# Power_Management.net
KiCad netlist of a schematic drawn in Altium Designer
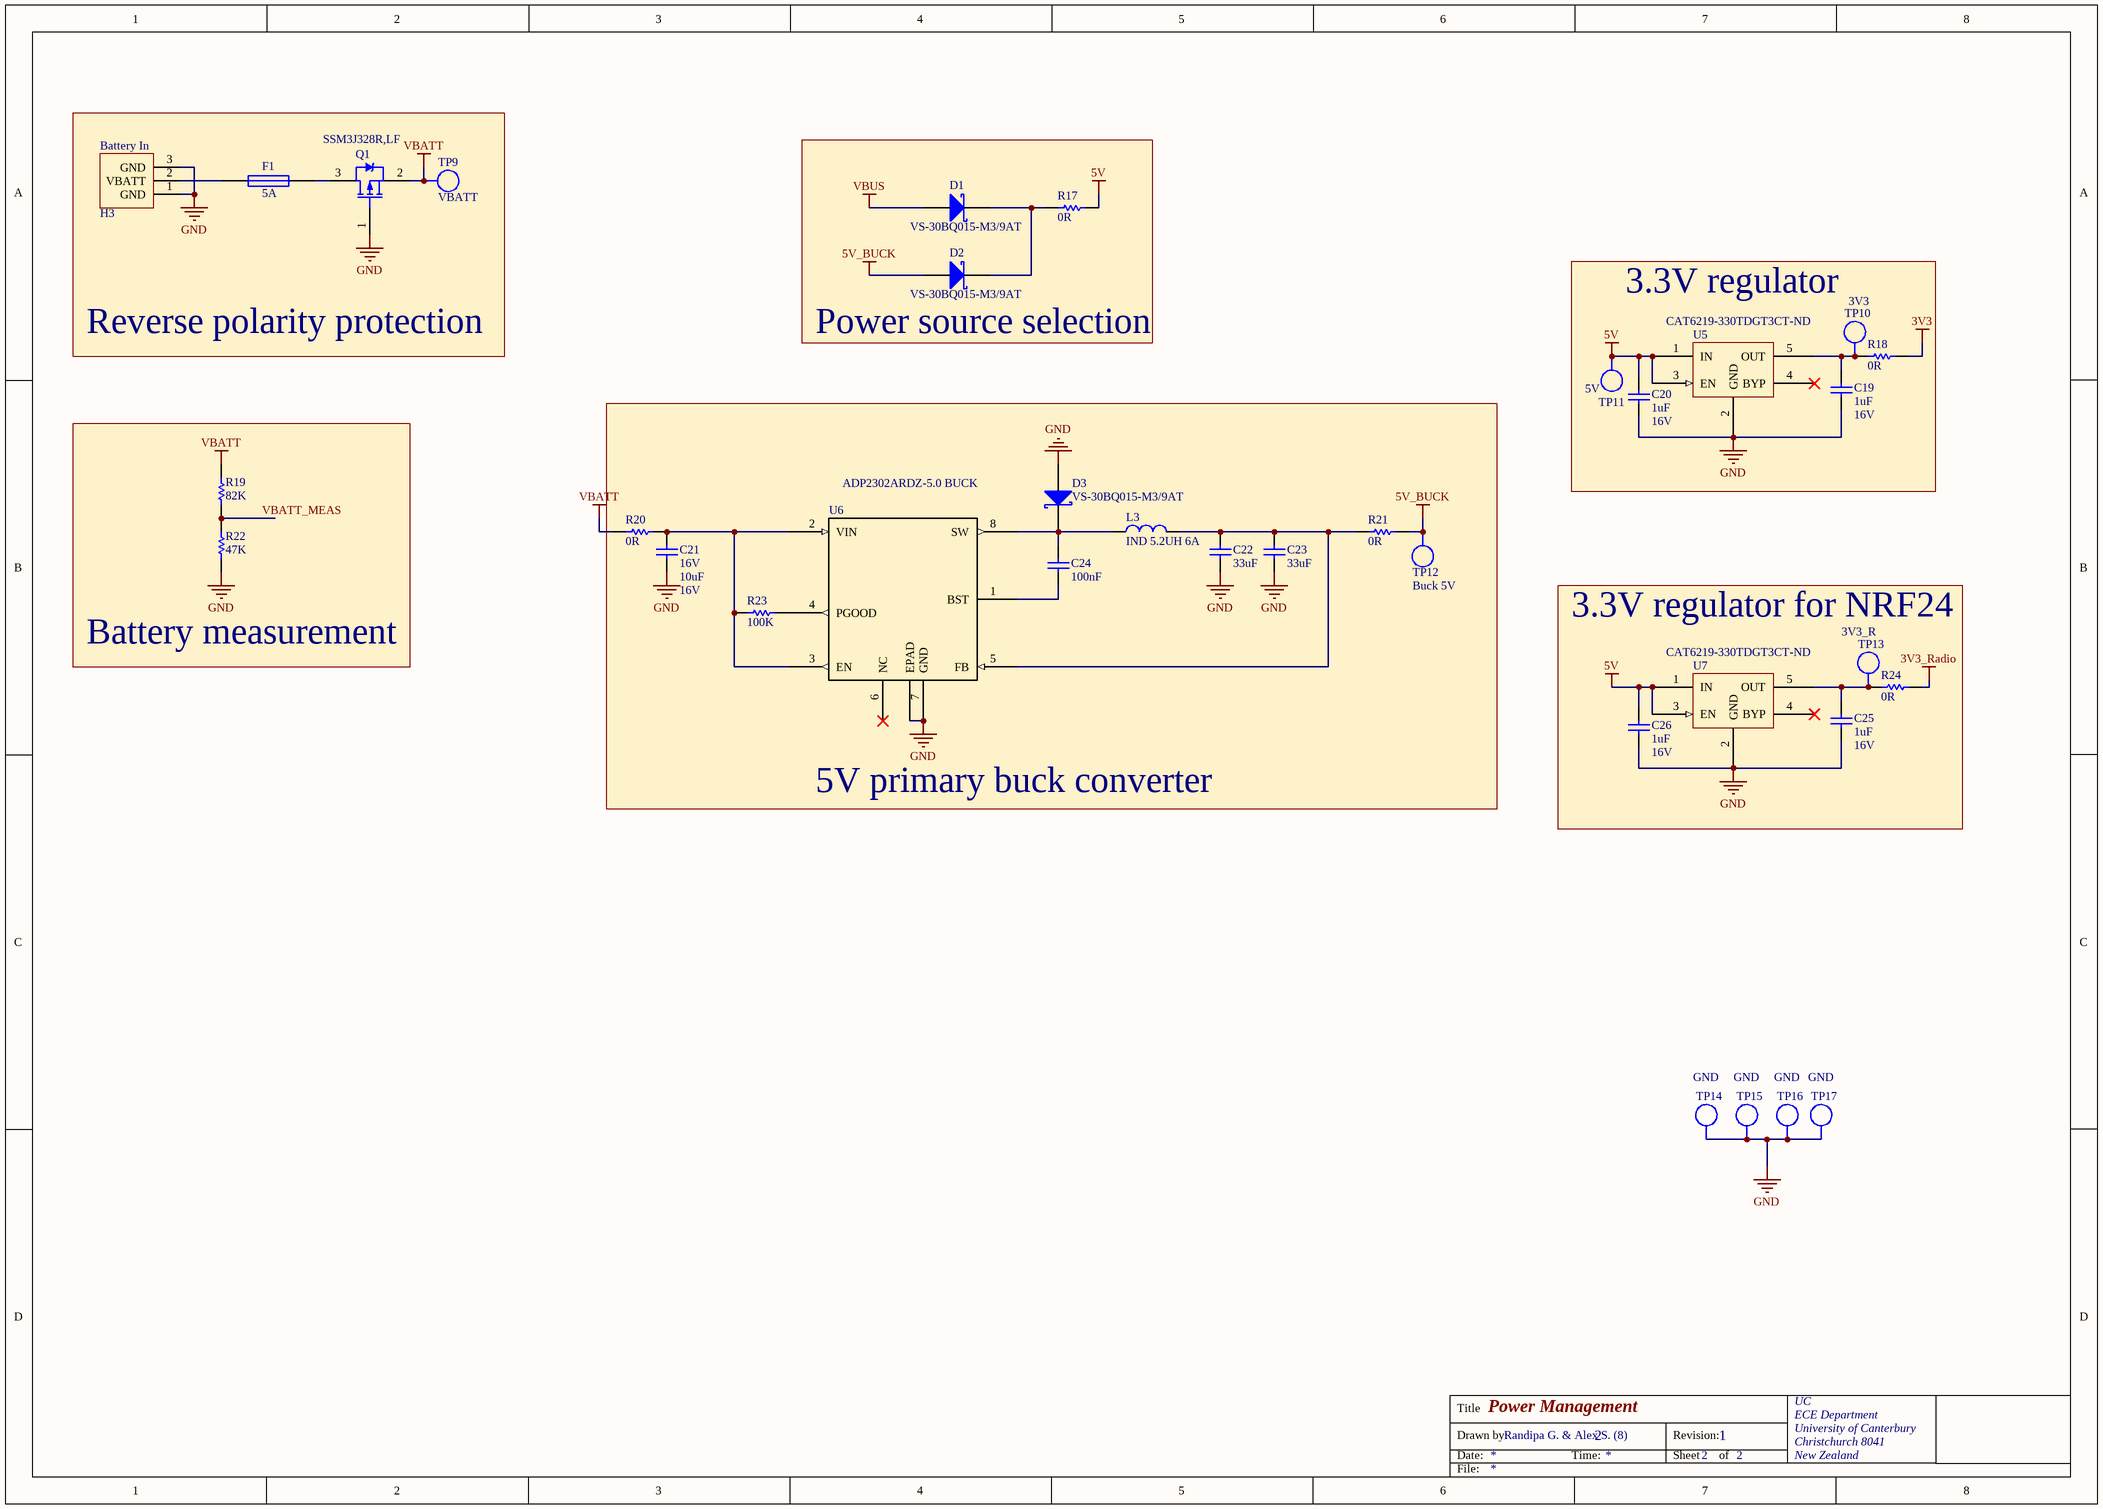
[diagram p0: Power Management.SchDoc]

(export (version "E")
  (design (tool "Eeschema 10.0.6"))
  (components
    (comp (ref "C19")
      (value "1uF")
      (footprint "CAPC1608L")
      (description "CAP CER 1uF Y5V -20% +80% 16V 0603")
      (fields (field (name "MAX VOLTAGE") "16V"))
      (libsource (lib "ECE AD19Components_19V1") (part "CC_1uF_0603"))
    )
    (comp (ref "C20")
      (value "1uF")
      (footprint "CAPC1608L")
      (description "CAP CER 1uF Y5V -20% +80% 16V 0603")
      (fields (field (name "MAX VOLTAGE") "16V"))
      (libsource (lib "ECE AD19Components_19V1") (part "CC_1uF_0603"))
    )
    (comp (ref "C21")
      (value "10uF")
      (footprint "CAPC2012L")
      (description "CAP CER 10uF X5R 16V 0805")
      (fields
        (field (name "MANUFACTURER") "Samsung Electro-Mechanics")
        (field (name "MANUFACTURER PART NUMBER") "CL21A106KOQNNWE")
        (field (name "VOLTAGE - RATED") "16V")
        (field (name "MAX VOLTAGE") "16V")
      )
      (libsource (lib "ENCE461AD19_19V2") (part "CC_10uF_16V_0805"))
    )
    (comp (ref "C22")
      (value "33uF")
      (footprint "CAPC2012L")
      (description "CAP CER 33uF X5R 6V3 0805")
      (fields
        (field (name "MANUFACTURER") "TDK Corporation")
        (field (name "MANUFACTURER PART NUMBER") "C2012X5R0J336M125AC")
      )
      (libsource (lib "ENCE461AD19_19V2") (part "CC_33uF_6V3_0805"))
    )
    (comp (ref "C23")
      (value "33uF")
      (footprint "CAPC2012L")
      (description "CAP CER 33uF X5R 6V3 0805")
      (fields
        (field (name "MANUFACTURER") "TDK Corporation")
        (field (name "MANUFACTURER PART NUMBER") "C2012X5R0J336M125AC")
      )
      (libsource (lib "ENCE461AD19_19V2") (part "CC_33uF_6V3_0805"))
    )
    (comp (ref "C24")
      (value "100nF")
      (footprint "CAPC1608L")
      (description "CAP CER 100nF X7R +-10% 50V 0603")
      (libsource (lib "ECE AD19Components_19V1") (part "CC_100nF_0603"))
    )
    (comp (ref "C25")
      (value "1uF")
      (footprint "CAPC1608L")
      (description "CAP CER 1uF Y5V -20% +80% 16V 0603")
      (fields (field (name "MAX VOLTAGE") "16V"))
      (libsource (lib "ECE AD19Components_19V1") (part "CC_1uF_0603"))
    )
    (comp (ref "C26")
      (value "1uF")
      (footprint "CAPC1608L")
      (description "CAP CER 1uF Y5V -20% +80% 16V 0603")
      (fields (field (name "MAX VOLTAGE") "16V"))
      (libsource (lib "ECE AD19Components_19V1") (part "CC_1uF_0603"))
    )
    (comp (ref "D1")
      (value "VS-30BQ015-M3/9AT")
      (footprint "SMC")
      (description "DIODE, SCHOTTKY, 3A, 15V, DO-214AB / SMC")
      (fields (field (name "MANUFACTURER") "Vishay Semiconductors"))
      (libsource (lib "ECE AD19Components_19V1") (part "DS_VS-30BQ015-M3"))
    )
    (comp (ref "D2")
      (value "VS-30BQ015-M3/9AT")
      (footprint "SMC")
      (description "DIODE, SCHOTTKY, 3A, 15V, DO-214AB / SMC")
      (fields (field (name "MANUFACTURER") "Vishay Semiconductors"))
      (libsource (lib "ECE AD19Components_19V1") (part "DS_VS-30BQ015-M3"))
    )
    (comp (ref "D3")
      (value "VS-30BQ015-M3/9AT")
      (footprint "SMC")
      (description "DIODE, SCHOTTKY, 3A, 15V, DO-214AB / SMC")
      (fields (field (name "MANUFACTURER") "Vishay Semiconductors"))
      (libsource (lib "ECE AD19Components_19V1") (part "DS_VS-30BQ015-M3"))
    )
    (comp (ref "F1")
      (value "5A")
      (footprint "RESC3216N")
      (description "Fuse 5.0A Fast Acting 1206 SMD")
      (fields (field (name "MANUFACTURER PART NUMBER") "C1F5") (field (name "MANUFACTURER") "Bel TRP"))
      (libsource (lib "ECE AD19Components_19V1") (part "FS_Fuse_5.0A"))
    )
    (comp (ref "H3")
      (value "Battery In")
      (footprint "BATT_HEADER_3POS")
      (description "3Pin Header 2.54mm spacing")
      (libsource (lib "ENCE461AD19_19V2") (part "Battery_HEADER_3pin"))
    )
    (comp (ref "L3")
      (value "IND 5.2UH 6A")
      (footprint "INDUCTOR5u2")
      (description "FIXED IND 5.2UH 6A 22 MOHM SMD")
      (fields
        (field (name "MANUFACTURER") "Sumida America Components Inc.")
        (field (name "MANUFACTURER PART NUMBER") "CDRH104RNP-5R2NC")
      )
      (libsource (lib "ENCE461AD19_19V2") (part "CDRH104RNP-5R2NC"))
    )
    (comp (ref "Q1")
      (value "SSM3J328R,LF")
      (footprint "SOT23_L")
      (description "MOSFET P-CH 20V 6A SOT23-3")
      (fields
        (field (name "MANUFACTURER") "Toshiba")
        (field (name "MANUFACTURER PART NUMBER") "SSM3J328R,LF")
      )
      (libsource (lib "ECE AD19Components_19V1") (part "TM_SSM3J328R"))
    )
    (comp (ref "R17")
      (value "0R")
      (footprint "RESC1608L")
      (description "RES 0.0 OHM 1/10W 5% 0603 SMD")
      (libsource (lib "ECE AD19Components_19V1") (part "RS_0R0"))
    )
    (comp (ref "R18")
      (value "0R")
      (footprint "RESC1608L")
      (description "RES 0.0 OHM 1/10W 5% 0603 SMD")
      (libsource (lib "ECE AD19Components_19V1") (part "RS_0R0"))
    )
    (comp (ref "R19")
      (value "82K")
      (footprint "RESC1608L")
      (description "RES 82.0K OHM 1/10W 5% 0603 SMD")
      (libsource (lib "ECE AD19Components_19V1") (part "RS_82K"))
    )
    (comp (ref "R20")
      (value "0R")
      (footprint "RESC1608L")
      (description "RES 0.0 OHM 1/10W 5% 0603 SMD")
      (libsource (lib "ECE AD19Components_19V1") (part "RS_0R0"))
    )
    (comp (ref "R21")
      (value "0R")
      (footprint "RESC1608L")
      (description "RES 0.0 OHM 1/10W 5% 0603 SMD")
      (libsource (lib "ECE AD19Components_19V1") (part "RS_0R0"))
    )
    (comp (ref "R22")
      (value "47K")
      (footprint "RESC1608L")
      (description "RES 47.0K OHM 1/10W 5% 0603 SMD")
      (libsource (lib "ECE AD19Components_19V1") (part "RS_47K"))
    )
    (comp (ref "R23")
      (value "100K")
      (footprint "RESC1608L")
      (description "RES 100K OHM 1/10W 5% 0603 SMD")
      (libsource (lib "ECE AD19Components_19V1") (part "RS_100K"))
    )
    (comp (ref "R24")
      (value "0R")
      (footprint "RESC1608L")
      (description "RES 0.0 OHM 1/10W 5% 0603 SMD")
      (libsource (lib "ECE AD19Components_19V1") (part "RS_0R0"))
    )
    (comp (ref "TP9")
      (value "VBATT")
      (footprint "TP_1206")
      (description "Test-Point 3.3x1.6x2.1mm SMD")
      (fields
        (field (name "MANUFACTURER") "Harwin Inc")
        (field (name "MANUFACTURER PART NUMBER") "S1751-46R")
      )
      (libsource (lib "ECE AD19Components_19V1") (part "TP_1206"))
    )
    (comp (ref "TP10")
      (value "3V3")
      (footprint "TP_1206")
      (description "Test-Point 3.3x1.6x2.1mm SMD")
      (fields
        (field (name "MANUFACTURER") "Harwin Inc")
        (field (name "MANUFACTURER PART NUMBER") "S1751-46R")
      )
      (libsource (lib "ECE AD19Components_19V1") (part "TP_1206"))
    )
    (comp (ref "TP11")
      (value "5V")
      (footprint "TP_1206")
      (description "Test-Point 3.3x1.6x2.1mm SMD")
      (fields
        (field (name "MANUFACTURER") "Harwin Inc")
        (field (name "MANUFACTURER PART NUMBER") "S1751-46R")
      )
      (libsource (lib "ECE AD19Components_19V1") (part "TP_1206"))
    )
    (comp (ref "TP12")
      (value "Buck 5V")
      (footprint "TP_1206")
      (description "Test-Point 3.3x1.6x2.1mm SMD")
      (fields
        (field (name "MANUFACTURER") "Harwin Inc")
        (field (name "MANUFACTURER PART NUMBER") "S1751-46R")
      )
      (libsource (lib "ECE AD19Components_19V1") (part "TP_1206"))
    )
    (comp (ref "TP13")
      (value "3V3_R")
      (footprint "TP_1206")
      (description "Test-Point 3.3x1.6x2.1mm SMD")
      (fields
        (field (name "MANUFACTURER") "Harwin Inc")
        (field (name "MANUFACTURER PART NUMBER") "S1751-46R")
      )
      (libsource (lib "ECE AD19Components_19V1") (part "TP_1206"))
    )
    (comp (ref "TP14")
      (value "GND")
      (footprint "TP_1206")
      (description "Test-Point 3.3x1.6x2.1mm SMD")
      (fields
        (field (name "MANUFACTURER") "Harwin Inc")
        (field (name "MANUFACTURER PART NUMBER") "S1751-46R")
      )
      (libsource (lib "ECE AD19Components_19V1") (part "TP_1206"))
    )
    (comp (ref "TP15")
      (value "GND")
      (footprint "TP_1206")
      (description "Test-Point 3.3x1.6x2.1mm SMD")
      (fields
        (field (name "MANUFACTURER") "Harwin Inc")
        (field (name "MANUFACTURER PART NUMBER") "S1751-46R")
      )
      (libsource (lib "ECE AD19Components_19V1") (part "TP_1206"))
    )
    (comp (ref "TP16")
      (value "GND")
      (footprint "TP_1206")
      (description "Test-Point 3.3x1.6x2.1mm SMD")
      (fields
        (field (name "MANUFACTURER") "Harwin Inc")
        (field (name "MANUFACTURER PART NUMBER") "S1751-46R")
      )
      (libsource (lib "ECE AD19Components_19V1") (part "TP_1206"))
    )
    (comp (ref "TP17")
      (value "GND")
      (footprint "TP_1206")
      (description "Test-Point 3.3x1.6x2.1mm SMD")
      (fields
        (field (name "MANUFACTURER") "Harwin Inc")
        (field (name "MANUFACTURER PART NUMBER") "S1751-46R")
      )
      (libsource (lib "ECE AD19Components_19V1") (part "TP_1206"))
    )
    (comp (ref "U5")
      (value "CAT6219-330TDGT3")
      (footprint "SOT95P280X145-5N")
      (description "IC REG LIN 3.3V 500MA TSOT23-5")
      (fields
        (field (name "BASE PART NUMBER") "CAT6219")
        (field (name "SUPPLIER PART NUMBER") "CAT6219-330TDGT3CT-ND")
      )
      (libsource (lib "ENCE461AD19_19V2") (part "SV_CAT6219-330TDGT3"))
    )
    (comp (ref "U6")
      (value "ADP2302ARDZ-5.0 BUCK")
      (footprint "RD_8_1")
      (description "IC REG BUCK 5V 2A 8SOIC")
      (fields (field (name "MANUFACTURER_PART_NUMBER") "ADP2302ARDZ-5.0-R7"))
      (libsource (lib "ENCE461AD19_19V2") (part "ADP2302ARDZ-5.0-R7"))
    )
    (comp (ref "U7")
      (value "CAT6219-330TDGT3")
      (footprint "SOT95P280X145-5N")
      (description "IC REG LIN 3.3V 500MA TSOT23-5")
      (fields
        (field (name "BASE PART NUMBER") "CAT6219")
        (field (name "SUPPLIER PART NUMBER") "CAT6219-330TDGT3CT-ND")
      )
      (libsource (lib "ENCE461AD19_19V2") (part "SV_CAT6219-330TDGT3"))
    )
  )
  (nets
    (net (code "1") (name "/VBATT_MEAS") (class "Default")
      (node (ref "R19") (pin "1") (pinfunction "1_1") (pintype "passive"))
      (node (ref "R22") (pin "2") (pinfunction "2_2") (pintype "passive"))
    )
    (net (code "2") (name "3V3") (class "Default")
      (node (ref "R18") (pin "1") (pinfunction "1_1") (pintype "passive"))
    )
    (net (code "3") (name "3V3_Radio") (class "Default")
      (node (ref "R24") (pin "1") (pinfunction "1_1") (pintype "passive"))
    )
    (net (code "4") (name "5V") (class "Default")
      (node (ref "C20") (pin "2") (pinfunction "2_2") (pintype "passive"))
      (node (ref "C26") (pin "2") (pinfunction "2_2") (pintype "passive"))
      (node (ref "R17") (pin "1") (pinfunction "1_1") (pintype "passive"))
      (node (ref "TP11") (pin "1") (pinfunction "1_1") (pintype "passive"))
      (node (ref "U5") (pin "1") (pinfunction "IN_1") (pintype "power_in"))
      (node (ref "U5") (pin "3") (pinfunction "EN_3") (pintype "input"))
      (node (ref "U7") (pin "1") (pinfunction "IN_1") (pintype "power_in"))
      (node (ref "U7") (pin "3") (pinfunction "EN_3") (pintype "input"))
    )
    (net (code "5") (name "5V_BUCK") (class "Default")
      (node (ref "D2") (pin "1") (pinfunction "A_1") (pintype "passive"))
      (node (ref "R21") (pin "1") (pinfunction "1_1") (pintype "passive"))
      (node (ref "TP12") (pin "1") (pinfunction "1_1") (pintype "passive"))
    )
    (net (code "6") (name "GND") (class "Default")
      (node (ref "C19") (pin "1") (pinfunction "1_1") (pintype "passive"))
      (node (ref "C20") (pin "1") (pinfunction "1_1") (pintype "passive"))
      (node (ref "C21") (pin "1") (pinfunction "1_1") (pintype "passive"))
      (node (ref "C22") (pin "1") (pinfunction "1_1") (pintype "passive"))
      (node (ref "C23") (pin "1") (pinfunction "1_1") (pintype "passive"))
      (node (ref "C25") (pin "1") (pinfunction "1_1") (pintype "passive"))
      (node (ref "C26") (pin "1") (pinfunction "1_1") (pintype "passive"))
      (node (ref "D3") (pin "1") (pinfunction "A_1") (pintype "passive"))
      (node (ref "H3") (pin "1") (pinfunction "GND_1") (pintype "passive"))
      (node (ref "H3") (pin "3") (pinfunction "GND_3") (pintype "passive"))
      (node (ref "Q1") (pin "1") (pinfunction "1_1") (pintype "passive"))
      (node (ref "R22") (pin "1") (pinfunction "1_1") (pintype "passive"))
      (node (ref "TP14") (pin "1") (pinfunction "1_1") (pintype "passive"))
      (node (ref "TP15") (pin "1") (pinfunction "1_1") (pintype "passive"))
      (node (ref "TP16") (pin "1") (pinfunction "1_1") (pintype "passive"))
      (node (ref "TP17") (pin "1") (pinfunction "1_1") (pintype "passive"))
      (node (ref "U5") (pin "2") (pinfunction "GND_2") (pintype "power_in"))
      (node (ref "U6") (pin "7") (pinfunction "GND_7") (pintype "power_in"))
      (node (ref "U6") (pin "EPAD") (pinfunction "EPAD_EPAD") (pintype "passive"))
      (node (ref "U7") (pin "2") (pinfunction "GND_2") (pintype "power_in"))
    )
    (net (code "7") (name "Net-(D1-K)") (class "Default")
      (node (ref "D1") (pin "2") (pinfunction "K_2") (pintype "passive"))
      (node (ref "D2") (pin "2") (pinfunction "K_2") (pintype "passive"))
      (node (ref "R17") (pin "2") (pinfunction "2_2") (pintype "passive"))
    )
    (net (code "8") (name "Net-(D3-K)") (class "Default")
      (node (ref "C24") (pin "2") (pinfunction "2_2") (pintype "passive"))
      (node (ref "D3") (pin "2") (pinfunction "K_2") (pintype "passive"))
      (node (ref "L3") (pin "1") (pintype "passive"))
      (node (ref "U6") (pin "8") (pinfunction "SW_8") (pintype "output"))
    )
    (net (code "9") (name "Net-(F1-Pad2)") (class "Default")
      (node (ref "F1") (pin "2") (pinfunction "2_2") (pintype "passive"))
      (node (ref "Q1") (pin "3") (pinfunction "3_3") (pintype "passive"))
    )
    (net (code "10") (name "Net-(H3-VBATT)") (class "Default")
      (node (ref "F1") (pin "1") (pinfunction "1_1") (pintype "passive"))
      (node (ref "H3") (pin "2") (pinfunction "VBATT_2") (pintype "passive"))
    )
    (net (code "11") (name "Net-(U5-OUT)") (class "Default")
      (node (ref "C19") (pin "2") (pinfunction "2_2") (pintype "passive"))
      (node (ref "R18") (pin "2") (pinfunction "2_2") (pintype "passive"))
      (node (ref "TP10") (pin "1") (pinfunction "1_1") (pintype "passive"))
      (node (ref "U5") (pin "5") (pinfunction "OUT_5") (pintype "power_in"))
    )
    (net (code "12") (name "Net-(U6-BST)") (class "Default")
      (node (ref "C24") (pin "1") (pinfunction "1_1") (pintype "passive"))
      (node (ref "U6") (pin "1") (pinfunction "BST_1") (pintype "passive"))
    )
    (net (code "13") (name "Net-(U6-EN)") (class "Default")
      (node (ref "C21") (pin "2") (pinfunction "2_2") (pintype "passive"))
      (node (ref "R20") (pin "1") (pinfunction "1_1") (pintype "passive"))
      (node (ref "R23") (pin "1") (pinfunction "1_1") (pintype "passive"))
      (node (ref "U6") (pin "2") (pinfunction "VIN_2") (pintype "input"))
      (node (ref "U6") (pin "3") (pinfunction "EN_3") (pintype "output"))
    )
    (net (code "14") (name "Net-(U6-FB)") (class "Default")
      (node (ref "C22") (pin "2") (pinfunction "2_2") (pintype "passive"))
      (node (ref "C23") (pin "2") (pinfunction "2_2") (pintype "passive"))
      (node (ref "L3") (pin "2") (pintype "passive"))
      (node (ref "R21") (pin "2") (pinfunction "2_2") (pintype "passive"))
      (node (ref "U6") (pin "5") (pinfunction "FB_5") (pintype "input"))
    )
    (net (code "15") (name "Net-(U6-PGOOD)") (class "Default")
      (node (ref "R23") (pin "2") (pinfunction "2_2") (pintype "passive"))
      (node (ref "U6") (pin "4") (pinfunction "PGOOD_4") (pintype "output"))
    )
    (net (code "16") (name "Net-(U7-OUT)") (class "Default")
      (node (ref "C25") (pin "2") (pinfunction "2_2") (pintype "passive"))
      (node (ref "R24") (pin "2") (pinfunction "2_2") (pintype "passive"))
      (node (ref "TP13") (pin "1") (pinfunction "1_1") (pintype "passive"))
      (node (ref "U7") (pin "5") (pinfunction "OUT_5") (pintype "power_in"))
    )
    (net (code "17") (name "VBATT") (class "Default")
      (node (ref "Q1") (pin "2") (pinfunction "2_2") (pintype "passive"))
      (node (ref "R19") (pin "2") (pinfunction "2_2") (pintype "passive"))
      (node (ref "R20") (pin "2") (pinfunction "2_2") (pintype "passive"))
      (node (ref "TP9") (pin "1") (pinfunction "1_1") (pintype "passive"))
    )
    (net (code "18") (name "VBUS") (class "Default")
      (node (ref "D1") (pin "1") (pinfunction "A_1") (pintype "passive"))
    )
    (net (code "19") (name "unconnected-(U5-BYP-Pad4)") (class "Default")
      (node (ref "U5") (pin "4") (pinfunction "BYP_4") (pintype "passive+no_connect"))
    )
    (net (code "20") (name "unconnected-(U6-NC-Pad6)") (class "Default")
      (node (ref "U6") (pin "6") (pinfunction "NC_6") (pintype "passive+no_connect"))
    )
    (net (code "21") (name "unconnected-(U7-BYP-Pad4)") (class "Default")
      (node (ref "U7") (pin "4") (pinfunction "BYP_4") (pintype "passive+no_connect"))
    )
  )
)
